# legatus_v0_2_with_notes.net
KiCad netlist of a schematic drawn in EAGLE
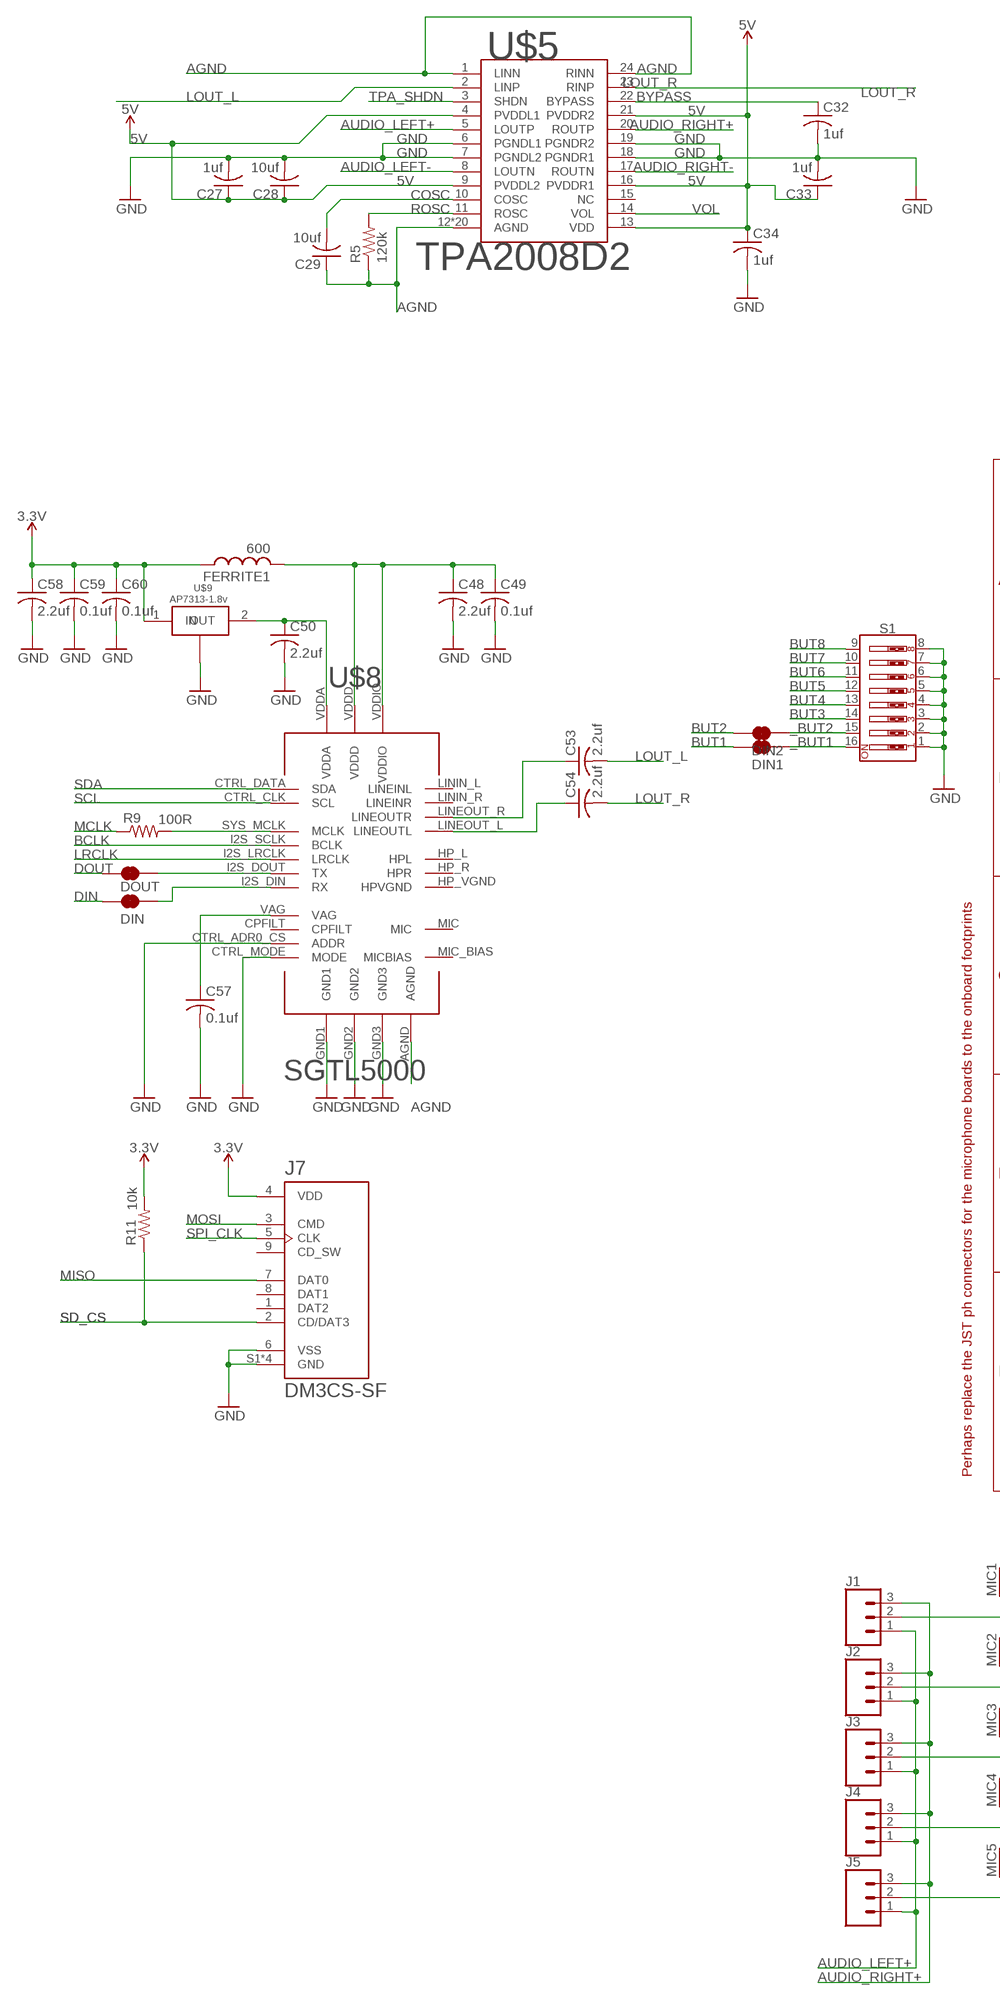
[diagram p0: schematic, sheet 1, part 1 of 2]
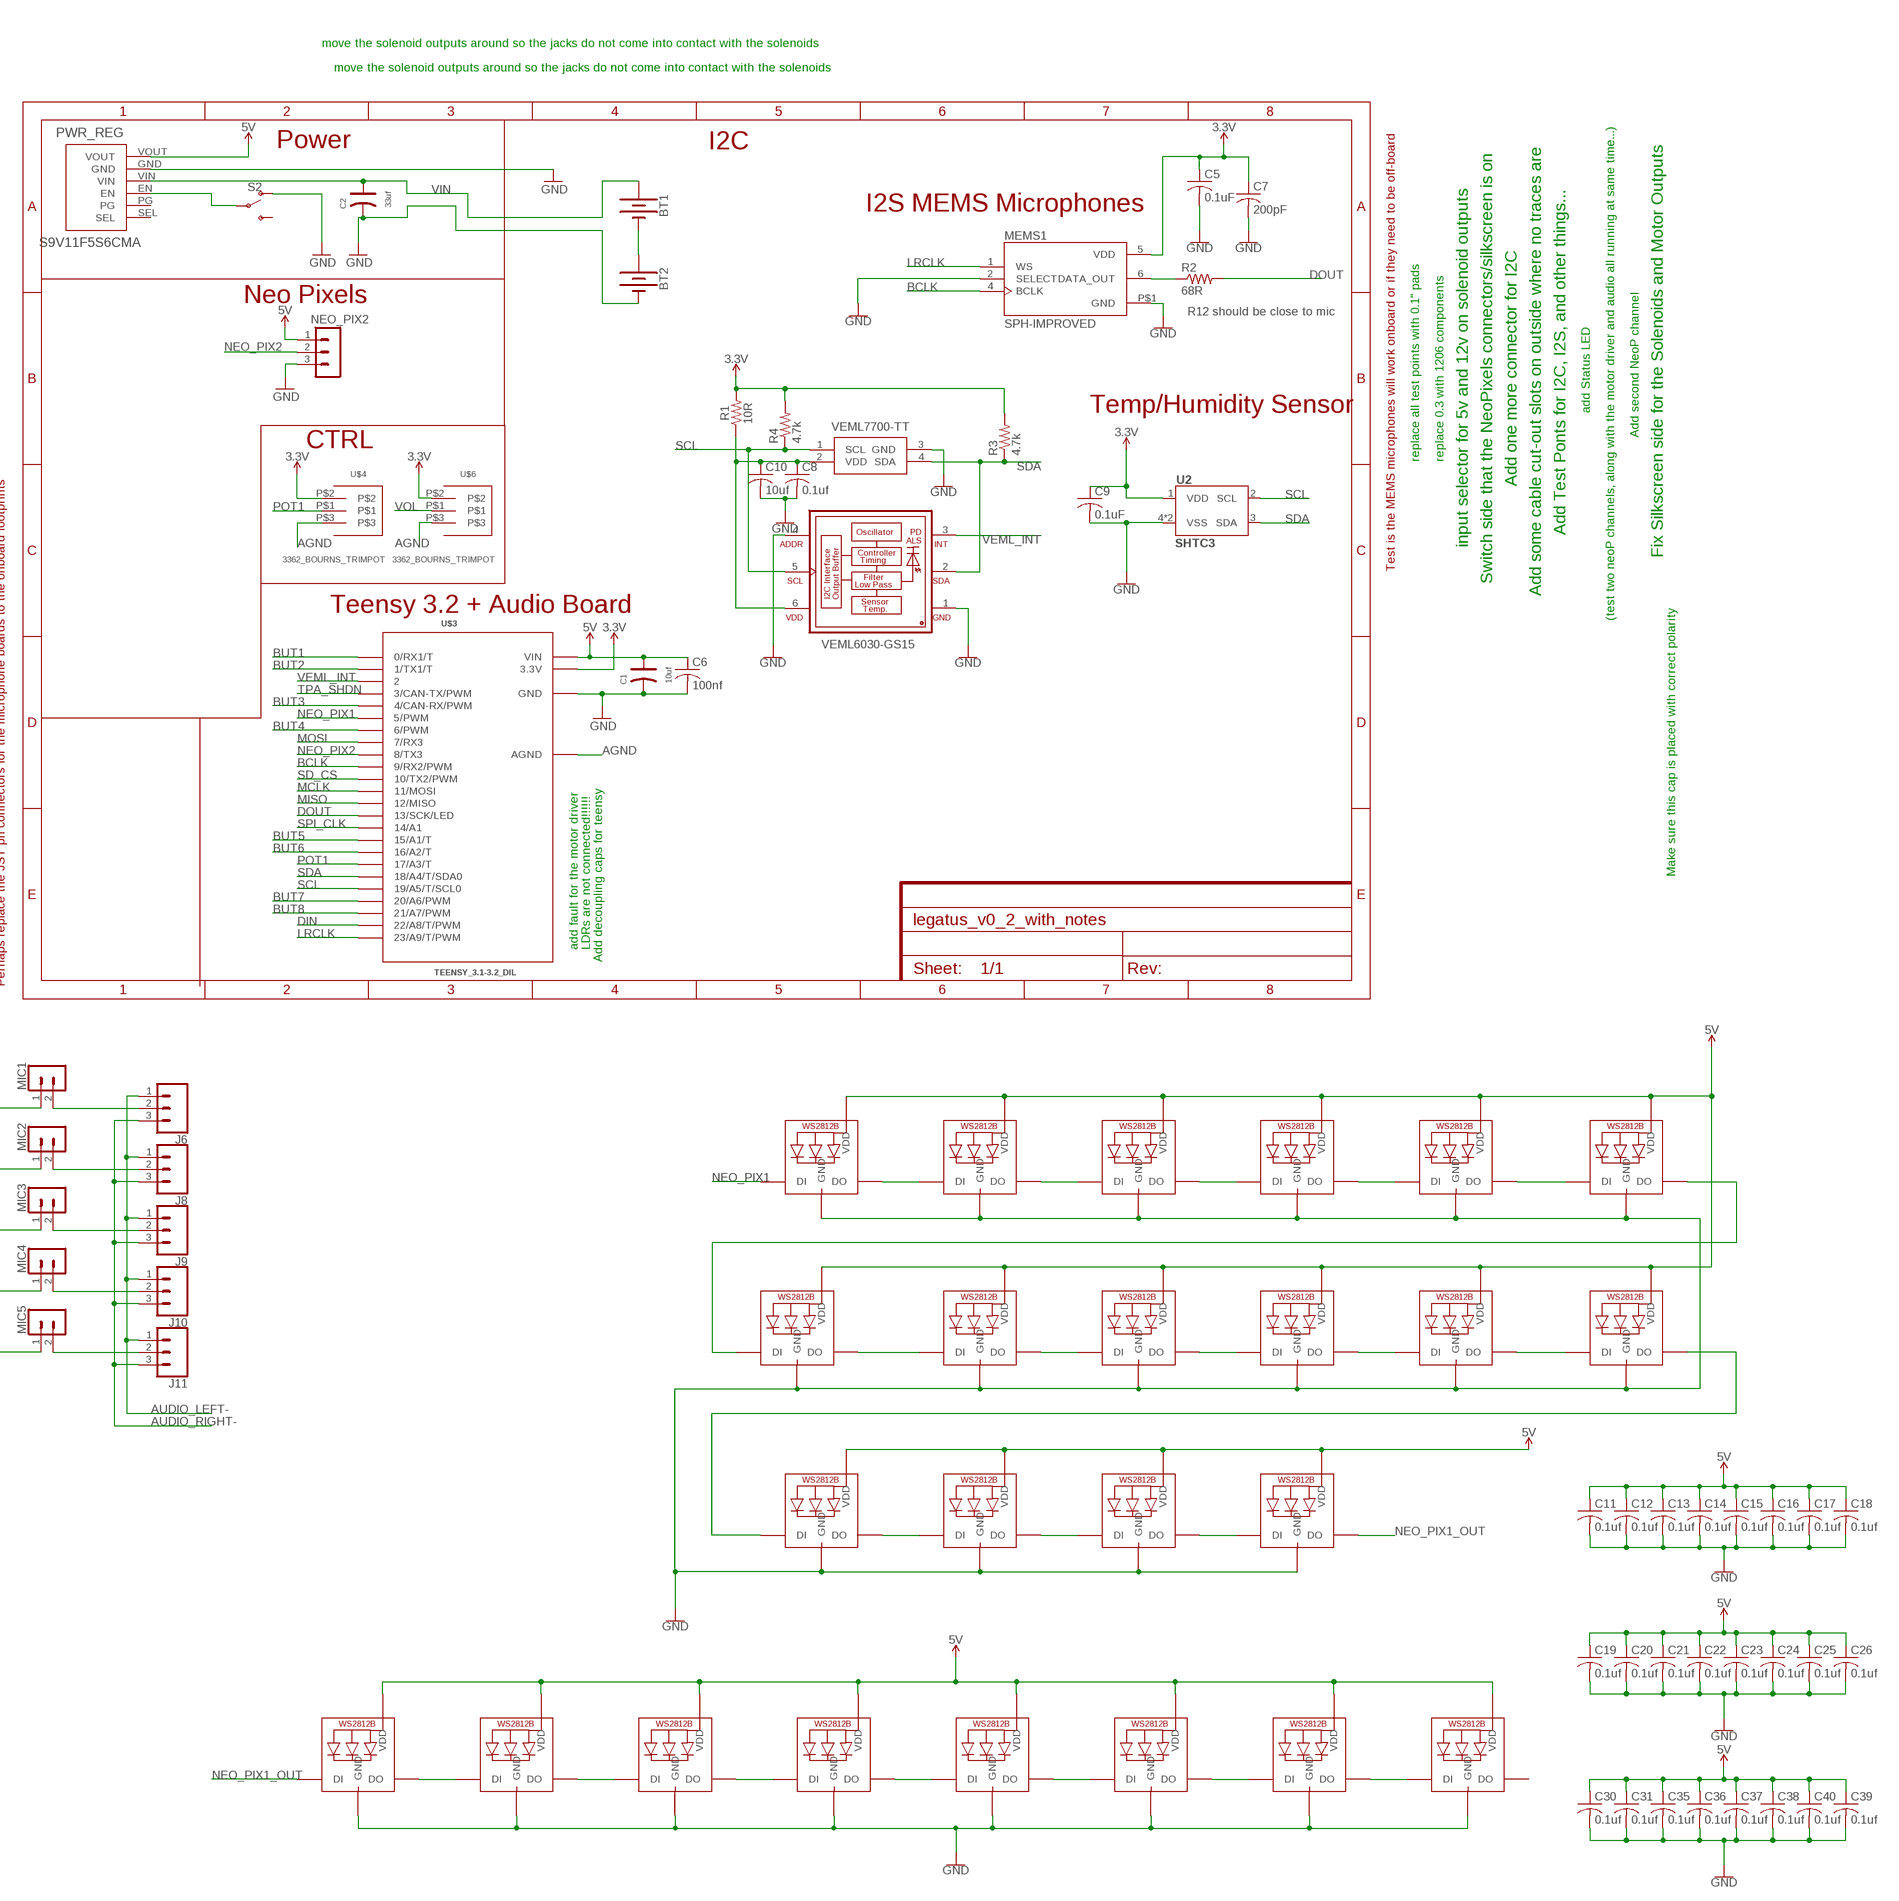
[diagram p1: schematic, sheet 1, part 2 of 2]

(export (version "E")
  (design (tool "Eeschema 10.0.6"))
  (components
    (comp (ref "BT1")
      (value "BATTERY-18650")
      (footprint "eagle-import:BATTERY_18650-HOLDER")
      (libsource (lib "eagle-import") (part "BATTERY-18650"))
    )
    (comp (ref "BT2")
      (value "BATTERY-18650")
      (footprint "eagle-import:BATTERY_18650-HOLDER")
      (libsource (lib "eagle-import") (part "BATTERY-18650"))
    )
    (comp (ref "C1")
      (value "10uf")
      (footprint "eagle-import:PC-D5.3MM")
      (fields (field (name "MPN") "KS 100uF/16V"))
      (libsource (lib "eagle-import") (part "DIP-ALUMINUM-47UF-16V(D5-H7MM)"))
    )
    (comp (ref "C2")
      (value "33uf")
      (footprint "eagle-import:PC-D5.3MM")
      (fields (field (name "MPN") "KS 100uF/16V"))
      (libsource (lib "eagle-import") (part "DIP-ALUMINUM-47UF-16V(D5-H7MM)"))
    )
    (comp (ref "C5")
      (value "0.1uF")
      (footprint "eagle-import:C0805")
      (libsource (lib "eagle-import") (part "rcl_334_C-USC0805"))
    )
    (comp (ref "C6")
      (value "100nf")
      (footprint "eagle-import:C2012")
      (libsource (lib "eagle-import") (part "C-USC2012"))
    )
    (comp (ref "C7")
      (value "200pF")
      (footprint "eagle-import:C0805")
      (libsource (lib "eagle-import") (part "rcl_334_C-USC0805"))
    )
    (comp (ref "C8")
      (value "0.1uf")
      (footprint "eagle-import:C0805")
      (libsource (lib "eagle-import") (part "rcl_334_C-USC0805"))
    )
    (comp (ref "C9")
      (value "0.1uF")
      (footprint "eagle-import:C0805")
      (libsource (lib "eagle-import") (part "rcl_334_C-USC0805"))
    )
    (comp (ref "C10")
      (value "10uf")
      (footprint "eagle-import:C0805")
      (libsource (lib "eagle-import") (part "rcl_334_C-USC0805"))
    )
    (comp (ref "C11")
      (value "0.1uf")
      (footprint "eagle-import:C0805")
      (libsource (lib "eagle-import") (part "rcl_334_C-USC0805"))
    )
    (comp (ref "C12")
      (value "0.1uf")
      (footprint "eagle-import:C0805")
      (libsource (lib "eagle-import") (part "rcl_334_C-USC0805"))
    )
    (comp (ref "C13")
      (value "0.1uf")
      (footprint "eagle-import:C0805")
      (libsource (lib "eagle-import") (part "rcl_334_C-USC0805"))
    )
    (comp (ref "C14")
      (value "0.1uf")
      (footprint "eagle-import:C0805")
      (libsource (lib "eagle-import") (part "rcl_334_C-USC0805"))
    )
    (comp (ref "C15")
      (value "0.1uf")
      (footprint "eagle-import:C0805")
      (libsource (lib "eagle-import") (part "rcl_334_C-USC0805"))
    )
    (comp (ref "C16")
      (value "0.1uf")
      (footprint "eagle-import:C0805")
      (libsource (lib "eagle-import") (part "rcl_334_C-USC0805"))
    )
    (comp (ref "C17")
      (value "0.1uf")
      (footprint "eagle-import:C0805")
      (libsource (lib "eagle-import") (part "rcl_334_C-USC0805"))
    )
    (comp (ref "C18")
      (value "0.1uf")
      (footprint "eagle-import:C0805")
      (libsource (lib "eagle-import") (part "rcl_334_C-USC0805"))
    )
    (comp (ref "C19")
      (value "0.1uf")
      (footprint "eagle-import:C0805")
      (libsource (lib "eagle-import") (part "rcl_334_C-USC0805"))
    )
    (comp (ref "C20")
      (value "0.1uf")
      (footprint "eagle-import:C0805")
      (libsource (lib "eagle-import") (part "rcl_334_C-USC0805"))
    )
    (comp (ref "C21")
      (value "0.1uf")
      (footprint "eagle-import:C0805")
      (libsource (lib "eagle-import") (part "rcl_334_C-USC0805"))
    )
    (comp (ref "C22")
      (value "0.1uf")
      (footprint "eagle-import:C0805")
      (libsource (lib "eagle-import") (part "rcl_334_C-USC0805"))
    )
    (comp (ref "C23")
      (value "0.1uf")
      (footprint "eagle-import:C0805")
      (libsource (lib "eagle-import") (part "rcl_334_C-USC0805"))
    )
    (comp (ref "C24")
      (value "0.1uf")
      (footprint "eagle-import:C0805")
      (libsource (lib "eagle-import") (part "rcl_334_C-USC0805"))
    )
    (comp (ref "C25")
      (value "0.1uf")
      (footprint "eagle-import:C0805")
      (libsource (lib "eagle-import") (part "rcl_334_C-USC0805"))
    )
    (comp (ref "C26")
      (value "0.1uf")
      (footprint "eagle-import:C0805")
      (libsource (lib "eagle-import") (part "rcl_334_C-USC0805"))
    )
    (comp (ref "C27")
      (value "1uf")
      (footprint "eagle-import:C0805")
      (libsource (lib "eagle-import") (part "rcl_334_C-USC0805"))
    )
    (comp (ref "C28")
      (value "10uf")
      (footprint "eagle-import:C0805")
      (libsource (lib "eagle-import") (part "rcl_334_C-USC0805"))
    )
    (comp (ref "C29")
      (value "10uf")
      (footprint "eagle-import:C0805")
      (libsource (lib "eagle-import") (part "rcl_334_C-USC0805"))
    )
    (comp (ref "C30")
      (value "0.1uf")
      (footprint "eagle-import:C0805")
      (libsource (lib "eagle-import") (part "rcl_334_C-USC0805"))
    )
    (comp (ref "C31")
      (value "0.1uf")
      (footprint "eagle-import:C0805")
      (libsource (lib "eagle-import") (part "rcl_334_C-USC0805"))
    )
    (comp (ref "C32")
      (value "1uf")
      (footprint "eagle-import:C0805")
      (libsource (lib "eagle-import") (part "rcl_334_C-USC0805"))
    )
    (comp (ref "C33")
      (value "1uf")
      (footprint "eagle-import:C0805")
      (libsource (lib "eagle-import") (part "rcl_334_C-USC0805"))
    )
    (comp (ref "C34")
      (value "1uf")
      (footprint "eagle-import:C0805")
      (libsource (lib "eagle-import") (part "rcl_334_C-USC0805"))
    )
    (comp (ref "C35")
      (value "0.1uf")
      (footprint "eagle-import:C0805")
      (libsource (lib "eagle-import") (part "rcl_334_C-USC0805"))
    )
    (comp (ref "C36")
      (value "0.1uf")
      (footprint "eagle-import:C0805")
      (libsource (lib "eagle-import") (part "rcl_334_C-USC0805"))
    )
    (comp (ref "C37")
      (value "0.1uf")
      (footprint "eagle-import:C0805")
      (libsource (lib "eagle-import") (part "rcl_334_C-USC0805"))
    )
    (comp (ref "C38")
      (value "0.1uf")
      (footprint "eagle-import:C0805")
      (libsource (lib "eagle-import") (part "rcl_334_C-USC0805"))
    )
    (comp (ref "C39")
      (value "0.1uf")
      (footprint "eagle-import:C0805")
      (libsource (lib "eagle-import") (part "rcl_334_C-USC0805"))
    )
    (comp (ref "C40")
      (value "0.1uf")
      (footprint "eagle-import:C0805")
      (libsource (lib "eagle-import") (part "rcl_334_C-USC0805"))
    )
    (comp (ref "C48")
      (value "2.2uf")
      (footprint "eagle-import:C0805")
      (libsource (lib "eagle-import") (part "rcl_334_C-USC0805"))
    )
    (comp (ref "C49")
      (value "0.1uf")
      (footprint "eagle-import:C0805")
      (libsource (lib "eagle-import") (part "rcl_334_C-USC0805"))
    )
    (comp (ref "C50")
      (value "2.2uf")
      (footprint "eagle-import:C0805")
      (libsource (lib "eagle-import") (part "rcl_334_C-USC0805"))
    )
    (comp (ref "C53")
      (value "2.2uf")
      (footprint "eagle-import:C0805")
      (libsource (lib "eagle-import") (part "rcl_334_C-USC0805"))
    )
    (comp (ref "C54")
      (value "2.2uf")
      (footprint "eagle-import:C0805")
      (libsource (lib "eagle-import") (part "rcl_334_C-USC0805"))
    )
    (comp (ref "C57")
      (value "0.1uf")
      (footprint "eagle-import:C0805")
      (libsource (lib "eagle-import") (part "rcl_334_C-USC0805"))
    )
    (comp (ref "C58")
      (value "2.2uf")
      (footprint "eagle-import:C0805")
      (libsource (lib "eagle-import") (part "rcl_334_C-USC0805"))
    )
    (comp (ref "C59")
      (value "0.1uf")
      (footprint "eagle-import:C0805")
      (libsource (lib "eagle-import") (part "rcl_334_C-USC0805"))
    )
    (comp (ref "C60")
      (value "0.1uf")
      (footprint "eagle-import:C0805")
      (libsource (lib "eagle-import") (part "rcl_334_C-USC0805"))
    )
    (comp (ref "DIN")
      (value "JUMPER-SMT_2_NC_TRACE_SILK")
      (footprint "eagle-import:SMT-JUMPER_2_NC_TRACE_SILK")
      (libsource (lib "eagle-import") (part "JUMPER-SMT_2_NC_TRACE_SILK"))
    )
    (comp (ref "DIN1")
      (value "JUMPER-SMT_2_NC_TRACE_SILK")
      (footprint "eagle-import:SMT-JUMPER_2_NC_TRACE_SILK")
      (libsource (lib "eagle-import") (part "JUMPER-SMT_2_NC_TRACE_SILK"))
    )
    (comp (ref "DIN2")
      (value "JUMPER-SMT_2_NC_TRACE_SILK")
      (footprint "eagle-import:SMT-JUMPER_2_NC_TRACE_SILK")
      (libsource (lib "eagle-import") (part "JUMPER-SMT_2_NC_TRACE_SILK"))
    )
    (comp (ref "DOUT")
      (value "JUMPER-SMT_2_NC_TRACE_SILK")
      (footprint "eagle-import:SMT-JUMPER_2_NC_TRACE_SILK")
      (libsource (lib "eagle-import") (part "JUMPER-SMT_2_NC_TRACE_SILK"))
    )
    (comp (ref "FERRITE1")
      (value "600")
      (footprint "eagle-import:RESC0805_N")
      (libsource (lib "eagle-import") (part "INDUCTOR_0805_N"))
    )
    (comp (ref "J1")
      (value "CONN_03")
      (footprint "eagle-import:1X03")
      (libsource (lib "eagle-import") (part "CONN_03"))
    )
    (comp (ref "J2")
      (value "CONN_03")
      (footprint "eagle-import:1X03")
      (libsource (lib "eagle-import") (part "CONN_03"))
    )
    (comp (ref "J3")
      (value "CONN_03")
      (footprint "eagle-import:1X03")
      (libsource (lib "eagle-import") (part "CONN_03"))
    )
    (comp (ref "J4")
      (value "CONN_03")
      (footprint "eagle-import:1X03")
      (libsource (lib "eagle-import") (part "CONN_03"))
    )
    (comp (ref "J5")
      (value "CONN_03")
      (footprint "eagle-import:1X03")
      (libsource (lib "eagle-import") (part "CONN_03"))
    )
    (comp (ref "J6")
      (value "CONN_03")
      (footprint "eagle-import:1X03")
      (libsource (lib "eagle-import") (part "CONN_03"))
    )
    (comp (ref "J7")
      (value "DM3CS-SF")
      (footprint "eagle-import:HRS_DM3CS-SF")
      (fields (field (name "MF") "Hirose"))
      (libsource (lib "eagle-import") (part "DM3CS-SF"))
    )
    (comp (ref "J8")
      (value "CONN_03")
      (footprint "eagle-import:1X03")
      (libsource (lib "eagle-import") (part "CONN_03"))
    )
    (comp (ref "J9")
      (value "CONN_03")
      (footprint "eagle-import:1X03")
      (libsource (lib "eagle-import") (part "CONN_03"))
    )
    (comp (ref "J10")
      (value "CONN_03")
      (footprint "eagle-import:1X03")
      (libsource (lib "eagle-import") (part "CONN_03"))
    )
    (comp (ref "J11")
      (value "CONN_03")
      (footprint "eagle-import:1X03")
      (libsource (lib "eagle-import") (part "CONN_03"))
    )
    (comp (ref "LED1")
      (value "WS2812B_5050N")
      (footprint "eagle-import:WS2812B-NARROW")
      (libsource (lib "eagle-import") (part "WS2812B_5050N"))
    )
    (comp (ref "LED2")
      (value "WS2812B_5050N")
      (footprint "eagle-import:WS2812B-NARROW")
      (libsource (lib "eagle-import") (part "WS2812B_5050N"))
    )
    (comp (ref "LED3")
      (value "WS2812B_5050N")
      (footprint "eagle-import:WS2812B-NARROW")
      (libsource (lib "eagle-import") (part "WS2812B_5050N"))
    )
    (comp (ref "LED4")
      (value "WS2812B_5050N")
      (footprint "eagle-import:WS2812B-NARROW")
      (libsource (lib "eagle-import") (part "WS2812B_5050N"))
    )
    (comp (ref "LED5")
      (value "WS2812B_5050N")
      (footprint "eagle-import:WS2812B-NARROW")
      (libsource (lib "eagle-import") (part "WS2812B_5050N"))
    )
    (comp (ref "LED6")
      (value "WS2812B_5050N")
      (footprint "eagle-import:WS2812B-NARROW")
      (libsource (lib "eagle-import") (part "WS2812B_5050N"))
    )
    (comp (ref "LED7")
      (value "WS2812B_5050N")
      (footprint "eagle-import:WS2812B-NARROW")
      (libsource (lib "eagle-import") (part "WS2812B_5050N"))
    )
    (comp (ref "LED8")
      (value "WS2812B_5050N")
      (footprint "eagle-import:WS2812B-NARROW")
      (libsource (lib "eagle-import") (part "WS2812B_5050N"))
    )
    (comp (ref "LED9")
      (value "WS2812B_5050N")
      (footprint "eagle-import:WS2812B-NARROW")
      (libsource (lib "eagle-import") (part "WS2812B_5050N"))
    )
    (comp (ref "LED10")
      (value "WS2812B_5050N")
      (footprint "eagle-import:WS2812B-NARROW")
      (libsource (lib "eagle-import") (part "WS2812B_5050N"))
    )
    (comp (ref "LED11")
      (value "WS2812B_5050N")
      (footprint "eagle-import:WS2812B-NARROW")
      (libsource (lib "eagle-import") (part "WS2812B_5050N"))
    )
    (comp (ref "LED12")
      (value "WS2812B_5050N")
      (footprint "eagle-import:WS2812B-NARROW")
      (libsource (lib "eagle-import") (part "WS2812B_5050N"))
    )
    (comp (ref "LED13")
      (value "WS2812B_5050N")
      (footprint "eagle-import:WS2812B-NARROW")
      (libsource (lib "eagle-import") (part "WS2812B_5050N"))
    )
    (comp (ref "LED14")
      (value "WS2812B_5050N")
      (footprint "eagle-import:WS2812B-NARROW")
      (libsource (lib "eagle-import") (part "WS2812B_5050N"))
    )
    (comp (ref "LED15")
      (value "WS2812B_5050N")
      (footprint "eagle-import:WS2812B-NARROW")
      (libsource (lib "eagle-import") (part "WS2812B_5050N"))
    )
    (comp (ref "LED16")
      (value "WS2812B_5050N")
      (footprint "eagle-import:WS2812B-NARROW")
      (libsource (lib "eagle-import") (part "WS2812B_5050N"))
    )
    (comp (ref "LED17")
      (value "WS2812B_5050N")
      (footprint "eagle-import:WS2812B-NARROW")
      (libsource (lib "eagle-import") (part "WS2812B_5050N"))
    )
    (comp (ref "LED18")
      (value "WS2812B_5050N")
      (footprint "eagle-import:WS2812B-NARROW")
      (libsource (lib "eagle-import") (part "WS2812B_5050N"))
    )
    (comp (ref "LED19")
      (value "WS2812B_5050N")
      (footprint "eagle-import:WS2812B-NARROW")
      (libsource (lib "eagle-import") (part "WS2812B_5050N"))
    )
    (comp (ref "LED20")
      (value "WS2812B_5050N")
      (footprint "eagle-import:WS2812B-NARROW")
      (libsource (lib "eagle-import") (part "WS2812B_5050N"))
    )
    (comp (ref "LED21")
      (value "WS2812B_5050N")
      (footprint "eagle-import:WS2812B-NARROW")
      (libsource (lib "eagle-import") (part "WS2812B_5050N"))
    )
    (comp (ref "LED22")
      (value "WS2812B_5050N")
      (footprint "eagle-import:WS2812B-NARROW")
      (libsource (lib "eagle-import") (part "WS2812B_5050N"))
    )
    (comp (ref "LED23")
      (value "WS2812B_5050N")
      (footprint "eagle-import:WS2812B-NARROW")
      (libsource (lib "eagle-import") (part "WS2812B_5050N"))
    )
    (comp (ref "LED24")
      (value "WS2812B_5050N")
      (footprint "eagle-import:WS2812B-NARROW")
      (libsource (lib "eagle-import") (part "WS2812B_5050N"))
    )
    (comp (ref "MEMS1")
      (value "SPH-IMPROVED")
      (footprint "eagle-import:MIC_SPH0645LM4H-B_LARGER_RING")
      (libsource (lib "eagle-import") (part "SPH-IMPROVED"))
    )
    (comp (ref "MIC1")
      (value "B2B-PH-K")
      (footprint "eagle-import:B2B-PH-K")
      (libsource (lib "eagle-import") (part "B2B-PH-K"))
    )
    (comp (ref "MIC2")
      (value "B2B-PH-K")
      (footprint "eagle-import:B2B-PH-K")
      (libsource (lib "eagle-import") (part "B2B-PH-K"))
    )
    (comp (ref "MIC3")
      (value "B2B-PH-K")
      (footprint "eagle-import:B2B-PH-K")
      (libsource (lib "eagle-import") (part "B2B-PH-K"))
    )
    (comp (ref "MIC4")
      (value "B2B-PH-K")
      (footprint "eagle-import:B2B-PH-K")
      (libsource (lib "eagle-import") (part "B2B-PH-K"))
    )
    (comp (ref "MIC5")
      (value "B2B-PH-K")
      (footprint "eagle-import:B2B-PH-K")
      (libsource (lib "eagle-import") (part "B2B-PH-K"))
    )
    (comp (ref "NEO_PIX2")
      (value "B3B-PH-K")
      (footprint "eagle-import:B3B-PH-K")
      (libsource (lib "eagle-import") (part "B3B-PH-K"))
    )
    (comp (ref "PWR_REG")
      (value "S9V11F5S6CMA")
      (footprint "eagle-import:S9V11F3S5CMA")
      (libsource (lib "eagle-import") (part "S9V11F5S6CMA"))
    )
    (comp (ref "R1")
      (value "10R")
      (footprint "eagle-import:R0805")
      (libsource (lib "eagle-import") (part "audio amplifier example_970892_R-US_R0805"))
    )
    (comp (ref "R2")
      (value "68R")
      (footprint "eagle-import:M0805")
      (libsource (lib "eagle-import") (part "R-US_M0805"))
    )
    (comp (ref "R3")
      (value "4.7k")
      (footprint "eagle-import:M0805")
      (libsource (lib "eagle-import") (part "R-US_M0805"))
    )
    (comp (ref "R4")
      (value "4.7k")
      (footprint "eagle-import:M0805")
      (libsource (lib "eagle-import") (part "R-US_M0805"))
    )
    (comp (ref "R5")
      (value "120k")
      (footprint "eagle-import:M0805")
      (libsource (lib "eagle-import") (part "R-US_M0805"))
    )
    (comp (ref "R9")
      (value "100R")
      (footprint "eagle-import:M0805")
      (libsource (lib "eagle-import") (part "rcl_R-US_M0805"))
    )
    (comp (ref "R11")
      (value "10k")
      (footprint "eagle-import:M0805")
      (libsource (lib "eagle-import") (part "rcl_R-US_M0805"))
    )
    (comp (ref "S1")
      (value "DIP-08-PTH")
      (footprint "eagle-import:DIPSWITCH-08")
      (libsource (lib "eagle-import") (part "DIP-08-PTH"))
    )
    (comp (ref "S2")
      (value "SWITCH-SPDT-PTH-11.6X4.0MM-LOCK")
      (footprint "eagle-import:SWITCH_SPDT_PTH_11.6X4.0MM_LOCK")
      (libsource (lib "eagle-import") (part "SWITCH-SPDT-PTH-11.6X4.0MM-LOCK"))
    )
    (comp (ref "U$3")
      (value "TEENSY_3.1-3.2_DIL")
      (footprint "eagle-import:TEENSY_3.0-3.2&LC_DIL")
      (libsource (lib "eagle-import") (part "TEENSY_3.1-3.2_DIL"))
    )
    (comp (ref "U$4")
      (value "3362_BOURNS_TRIMPOT")
      (footprint "eagle-import:3362_BOURNS_TRIMPOT")
      (libsource (lib "eagle-import") (part "3362_BOURNS_TRIMPOT"))
    )
    (comp (ref "U$5")
      (value "TPA2008D2")
      (footprint "eagle-import:PWP-TSSOP24")
      (libsource (lib "eagle-import") (part "TPA2008D2"))
    )
    (comp (ref "U$6")
      (value "3362_BOURNS_TRIMPOT")
      (footprint "eagle-import:3362_BOURNS_TRIMPOT")
      (libsource (lib "eagle-import") (part "3362_BOURNS_TRIMPOT"))
    )
    (comp (ref "U$8")
      (value "SGTL5000")
      (footprint "eagle-import:QFN-32-5X5MM")
      (libsource (lib "eagle-import") (part "SGTL5000"))
    )
    (comp (ref "U$9")
      (value "AP7313-1.8v")
      (footprint "eagle-import:SOT-23")
      (libsource (lib "eagle-import") (part "AP7313"))
    )
    (comp (ref "U2")
      (value "SHTC3")
      (footprint "eagle-import:SHTC3")
      (libsource (lib "eagle-import") (part "SHTC3"))
    )
    (comp (ref "VEML1")
      (value "VEML7700-TT")
      (footprint "eagle-import:VEML7700")
      (fields (field (name "MOUSER_PART_NUMBER") "78-VEML7700-TT") (field (name "RS_PART_NUMBER") "1226791P"))
      (libsource (lib "eagle-import") (part "VEML7700-TT"))
    )
    (comp (ref "VMEL1")
      (value "VEML6030-GS15")
      (footprint "eagle-import:VISHAY_VEML6030_2X2X0.87")
      (fields (field (name "MF") "Vishay Semiconductor"))
      (libsource (lib "eagle-import") (part "VEML6030-GS15"))
    )
  )
  (nets
    (net (code "1") (name "/AGND") (class "Default")
      (node (ref "C29") (pin "1") (pinfunction "1_1") (pintype "passive"))
      (node (ref "R5") (pin "1") (pinfunction "1_1") (pintype "passive"))
      (node (ref "U$3") (pin "AGND") (pinfunction "AGND_AGND") (pintype "power_in"))
      (node (ref "U$4") (pin "P$3") (pinfunction "P$3_P$3") (pintype "bidirectional"))
      (node (ref "U$5") (pin "1") (pinfunction "LINN_1") (pintype "bidirectional"))
      (node (ref "U$5") (pin "12") (pinfunction "AGND_12") (pintype "bidirectional"))
      (node (ref "U$5") (pin "24") (pinfunction "RINN_24") (pintype "bidirectional"))
      (node (ref "U$5") (pin "EXP") (pinfunction "AGND_EXP") (pintype "bidirectional"))
      (node (ref "U$5") (pin "EXP@1") (pinfunction "AGND_EXP@1") (pintype "bidirectional"))
      (node (ref "U$5") (pin "EXP@10") (pinfunction "AGND_EXP@10") (pintype "bidirectional"))
      (node (ref "U$5") (pin "EXP@11") (pinfunction "AGND_EXP@11") (pintype "bidirectional"))
      (node (ref "U$5") (pin "EXP@12") (pinfunction "AGND_EXP@12") (pintype "bidirectional"))
      (node (ref "U$5") (pin "EXP@13") (pinfunction "AGND_EXP@13") (pintype "bidirectional"))
      (node (ref "U$5") (pin "EXP@14") (pinfunction "AGND_EXP@14") (pintype "bidirectional"))
      (node (ref "U$5") (pin "EXP@15") (pinfunction "AGND_EXP@15") (pintype "bidirectional"))
      (node (ref "U$5") (pin "EXP@16") (pinfunction "AGND_EXP@16") (pintype "bidirectional"))
      (node (ref "U$5") (pin "EXP@17") (pinfunction "AGND_EXP@17") (pintype "bidirectional"))
      (node (ref "U$5") (pin "EXP@18") (pinfunction "AGND_EXP@18") (pintype "bidirectional"))
      (node (ref "U$5") (pin "EXP@2") (pinfunction "AGND_EXP@2") (pintype "bidirectional"))
      (node (ref "U$5") (pin "EXP@3") (pinfunction "AGND_EXP@3") (pintype "bidirectional"))
      (node (ref "U$5") (pin "EXP@4") (pinfunction "AGND_EXP@4") (pintype "bidirectional"))
      (node (ref "U$5") (pin "EXP@5") (pinfunction "AGND_EXP@5") (pintype "bidirectional"))
      (node (ref "U$5") (pin "EXP@6") (pinfunction "AGND_EXP@6") (pintype "bidirectional"))
      (node (ref "U$5") (pin "EXP@7") (pinfunction "AGND_EXP@7") (pintype "bidirectional"))
      (node (ref "U$5") (pin "EXP@8") (pinfunction "AGND_EXP@8") (pintype "bidirectional"))
      (node (ref "U$5") (pin "EXP@9") (pinfunction "AGND_EXP@9") (pintype "bidirectional"))
      (node (ref "U$6") (pin "P$3") (pinfunction "P$3_P$3") (pintype "bidirectional"))
      (node (ref "U$8") (pin "AGND") (pinfunction "AGND_AGND") (pintype "bidirectional"))
    )
    (net (code "2") (name "/AUDIO_LEFT+") (class "Default")
      (node (ref "J1") (pin "1") (pinfunction "1_1") (pintype "passive"))
      (node (ref "J2") (pin "1") (pinfunction "1_1") (pintype "passive"))
      (node (ref "J3") (pin "1") (pinfunction "1_1") (pintype "passive"))
      (node (ref "J4") (pin "1") (pinfunction "1_1") (pintype "passive"))
      (node (ref "J5") (pin "1") (pinfunction "1_1") (pintype "passive"))
      (node (ref "U$5") (pin "5") (pinfunction "LOUTP_5") (pintype "bidirectional"))
    )
    (net (code "3") (name "/AUDIO_LEFT-") (class "Default")
      (node (ref "J10") (pin "1") (pinfunction "1_1") (pintype "passive"))
      (node (ref "J11") (pin "1") (pinfunction "1_1") (pintype "passive"))
      (node (ref "J6") (pin "1") (pinfunction "1_1") (pintype "passive"))
      (node (ref "J8") (pin "1") (pinfunction "1_1") (pintype "passive"))
      (node (ref "J9") (pin "1") (pinfunction "1_1") (pintype "passive"))
      (node (ref "U$5") (pin "8") (pinfunction "LOUTN_8") (pintype "bidirectional"))
    )
    (net (code "4") (name "/AUDIO_RIGHT+") (class "Default")
      (node (ref "J1") (pin "3") (pinfunction "3_3") (pintype "passive"))
      (node (ref "J2") (pin "3") (pinfunction "3_3") (pintype "passive"))
      (node (ref "J3") (pin "3") (pinfunction "3_3") (pintype "passive"))
      (node (ref "J4") (pin "3") (pinfunction "3_3") (pintype "passive"))
      (node (ref "J5") (pin "3") (pinfunction "3_3") (pintype "passive"))
      (node (ref "U$5") (pin "20") (pinfunction "ROUTP_20") (pintype "bidirectional"))
    )
    (net (code "5") (name "/AUDIO_RIGHT-") (class "Default")
      (node (ref "J10") (pin "3") (pinfunction "3_3") (pintype "passive"))
      (node (ref "J11") (pin "3") (pinfunction "3_3") (pintype "passive"))
      (node (ref "J6") (pin "3") (pinfunction "3_3") (pintype "passive"))
      (node (ref "J8") (pin "3") (pinfunction "3_3") (pintype "passive"))
      (node (ref "J9") (pin "3") (pinfunction "3_3") (pintype "passive"))
      (node (ref "U$5") (pin "17") (pinfunction "ROUTN_17") (pintype "bidirectional"))
    )
    (net (code "6") (name "/BCLK") (class "Default")
      (node (ref "MEMS1") (pin "4") (pinfunction "BCLK_4") (pintype "input"))
      (node (ref "U$3") (pin "9") (pinfunction "9/RX2/PWM_9") (pintype "bidirectional"))
      (node (ref "U$8") (pin "I2S_SCLK") (pinfunction "BCLK_I2S_SCLK") (pintype "bidirectional"))
    )
    (net (code "7") (name "/BUT1") (class "Default")
      (node (ref "DIN1") (pin "1") (pinfunction "1_1") (pintype "passive"))
      (node (ref "U$3") (pin "0") (pinfunction "0/RX1/T_0") (pintype "bidirectional"))
    )
    (net (code "8") (name "/BUT2") (class "Default")
      (node (ref "DIN2") (pin "1") (pinfunction "1_1") (pintype "passive"))
      (node (ref "U$3") (pin "1") (pinfunction "1/TX1/T_1") (pintype "bidirectional"))
    )
    (net (code "9") (name "/BUT3") (class "Default")
      (node (ref "S1") (pin "14") (pinfunction "14_14") (pintype "passive"))
      (node (ref "U$3") (pin "4") (pinfunction "4/CAN-RX/PWM_4") (pintype "bidirectional"))
    )
    (net (code "10") (name "/BUT4") (class "Default")
      (node (ref "S1") (pin "13") (pinfunction "13_13") (pintype "passive"))
      (node (ref "U$3") (pin "6") (pinfunction "6/PWM_6") (pintype "bidirectional"))
    )
    (net (code "11") (name "/BUT5") (class "Default")
      (node (ref "S1") (pin "12") (pinfunction "12_12") (pintype "passive"))
      (node (ref "U$3") (pin "15/A1") (pinfunction "15/A1/T_15/A1") (pintype "bidirectional"))
    )
    (net (code "12") (name "/BUT6") (class "Default")
      (node (ref "S1") (pin "11") (pinfunction "11_11") (pintype "passive"))
      (node (ref "U$3") (pin "16/A2") (pinfunction "16/A2/T_16/A2") (pintype "bidirectional"))
    )
    (net (code "13") (name "/BUT7") (class "Default")
      (node (ref "S1") (pin "10") (pinfunction "10_10") (pintype "passive"))
      (node (ref "U$3") (pin "20/A6") (pinfunction "20/A6/PWM_20/A6") (pintype "bidirectional"))
    )
    (net (code "14") (name "/BUT8") (class "Default")
      (node (ref "S1") (pin "9") (pinfunction "9_9") (pintype "passive"))
      (node (ref "U$3") (pin "21/A7") (pinfunction "21/A7/PWM_21/A7") (pintype "bidirectional"))
    )
    (net (code "15") (name "/BYPASS") (class "Default")
      (node (ref "C32") (pin "1") (pinfunction "1_1") (pintype "passive"))
      (node (ref "U$5") (pin "22") (pinfunction "BYPASS_22") (pintype "bidirectional"))
    )
    (net (code "16") (name "/COSC") (class "Default")
      (node (ref "C29") (pin "2") (pinfunction "2_2") (pintype "passive"))
      (node (ref "U$5") (pin "10") (pinfunction "COSC_10") (pintype "bidirectional"))
    )
    (net (code "17") (name "/DIN") (class "Default")
      (node (ref "DIN") (pin "1") (pinfunction "1_1") (pintype "passive"))
      (node (ref "U$3") (pin "22/A8") (pinfunction "22/A8/T/PWM_22/A8") (pintype "bidirectional"))
    )
    (net (code "18") (name "/DOUT") (class "Default")
      (node (ref "DOUT") (pin "1") (pinfunction "1_1") (pintype "passive"))
      (node (ref "R2") (pin "2") (pinfunction "2_2") (pintype "passive"))
      (node (ref "U$3") (pin "13") (pinfunction "13/SCK/LED_13") (pintype "bidirectional"))
    )
    (net (code "19") (name "/LOUT_L") (class "Default")
      (node (ref "C53") (pin "2") (pinfunction "2_2") (pintype "passive"))
      (node (ref "U$5") (pin "2") (pinfunction "LINP_2") (pintype "bidirectional"))
    )
    (net (code "20") (name "/LOUT_R") (class "Default")
      (node (ref "C54") (pin "2") (pinfunction "2_2") (pintype "passive"))
      (node (ref "U$5") (pin "23") (pinfunction "RINP_23") (pintype "bidirectional"))
    )
    (net (code "21") (name "/LRCLK") (class "Default")
      (node (ref "MEMS1") (pin "1") (pinfunction "WS_1") (pintype "input"))
      (node (ref "U$3") (pin "23/A9") (pinfunction "23/A9/T/PWM_23/A9") (pintype "bidirectional"))
      (node (ref "U$8") (pin "I2S_LRCLK") (pinfunction "LRCLK_I2S_LRCLK") (pintype "bidirectional"))
    )
    (net (code "22") (name "/MCLK") (class "Default")
      (node (ref "R9") (pin "1") (pinfunction "1_1") (pintype "passive"))
      (node (ref "U$3") (pin "11") (pinfunction "11/MOSI_11") (pintype "bidirectional"))
    )
    (net (code "23") (name "/MISO") (class "Default")
      (node (ref "J7") (pin "7") (pinfunction "DAT0_7") (pintype "passive"))
      (node (ref "U$3") (pin "12") (pinfunction "12/MISO_12") (pintype "bidirectional"))
    )
    (net (code "24") (name "/MOSI") (class "Default")
      (node (ref "J7") (pin "3") (pinfunction "CMD_3") (pintype "passive"))
      (node (ref "U$3") (pin "7") (pinfunction "7/RX3_7") (pintype "bidirectional"))
    )
    (net (code "25") (name "/NEO_PIX1") (class "Default")
      (node (ref "LED1") (pin "4-DIN") (pinfunction "DI_4-DIN") (pintype "input"))
      (node (ref "U$3") (pin "5") (pinfunction "5/PWM_5") (pintype "bidirectional"))
    )
    (net (code "26") (name "/NEO_PIX1_OUT") (class "Default")
      (node (ref "LED16") (pin "2-DOUT") (pinfunction "DO_2-DOUT") (pintype "output"))
      (node (ref "LED17") (pin "4-DIN") (pinfunction "DI_4-DIN") (pintype "input"))
    )
    (net (code "27") (name "/NEO_PIX2") (class "Default")
      (node (ref "NEO_PIX2") (pin "2") (pinfunction "2_2") (pintype "passive"))
      (node (ref "U$3") (pin "8") (pinfunction "8/TX3_8") (pintype "bidirectional"))
    )
    (net (code "28") (name "/POT1") (class "Default")
      (node (ref "U$3") (pin "17/A3") (pinfunction "17/A3/T_17/A3") (pintype "bidirectional"))
      (node (ref "U$4") (pin "P$1") (pinfunction "P$1_P$1") (pintype "bidirectional"))
    )
    (net (code "29") (name "/ROSC") (class "Default")
      (node (ref "R5") (pin "2") (pinfunction "2_2") (pintype "passive"))
      (node (ref "U$5") (pin "11") (pinfunction "ROSC_11") (pintype "bidirectional"))
    )
    (net (code "30") (name "/SCL") (class "Default")
      (node (ref "R4") (pin "1") (pinfunction "1_1") (pintype "passive"))
      (node (ref "U$3") (pin "19/A5") (pinfunction "19/A5/T/SCL0_19/A5") (pintype "bidirectional"))
      (node (ref "U$8") (pin "CTRL_CLK") (pinfunction "SCL_CTRL_CLK") (pintype "bidirectional"))
      (node (ref "U2") (pin "2") (pinfunction "SCL_2") (pintype "bidirectional"))
      (node (ref "VEML1") (pin "1") (pinfunction "SCL_1") (pintype "bidirectional"))
      (node (ref "VMEL1") (pin "5") (pinfunction "SCL_5") (pintype "input"))
    )
    (net (code "31") (name "/SDA") (class "Default")
      (node (ref "R3") (pin "1") (pinfunction "1_1") (pintype "passive"))
      (node (ref "U$3") (pin "18/A4") (pinfunction "18/A4/T/SDA0_18/A4") (pintype "bidirectional"))
      (node (ref "U$8") (pin "CTRL_DATA") (pinfunction "SDA_CTRL_DATA") (pintype "bidirectional"))
      (node (ref "U2") (pin "3") (pinfunction "SDA_3") (pintype "bidirectional"))
      (node (ref "VEML1") (pin "4") (pinfunction "SDA_4") (pintype "bidirectional"))
      (node (ref "VMEL1") (pin "2") (pinfunction "SDA_2") (pintype "bidirectional"))
    )
    (net (code "32") (name "/SD_CS") (class "Default")
      (node (ref "J7") (pin "2") (pinfunction "CD/DAT3_2") (pintype "passive"))
      (node (ref "R11") (pin "1") (pinfunction "1_1") (pintype "passive"))
      (node (ref "U$3") (pin "10") (pinfunction "10/TX2/PWM_10") (pintype "bidirectional"))
    )
    (net (code "33") (name "/SPI_CLK") (class "Default")
      (node (ref "J7") (pin "5") (pinfunction "CLK_5") (pintype "passive"))
      (node (ref "U$3") (pin "14/A0") (pinfunction "14/A1_14/A0") (pintype "bidirectional"))
    )
    (net (code "34") (name "/TPA_SHDN") (class "Default")
      (node (ref "U$3") (pin "3") (pinfunction "3/CAN-TX/PWM_3") (pintype "bidirectional"))
      (node (ref "U$5") (pin "3") (pinfunction "SHDN_3") (pintype "bidirectional"))
    )
    (net (code "35") (name "/VEML_INT") (class "Default")
      (node (ref "U$3") (pin "2") (pinfunction "2_2") (pintype "bidirectional"))
      (node (ref "VMEL1") (pin "3") (pinfunction "INT_3") (pintype "output"))
    )
    (net (code "36") (name "/VIN") (class "Default")
      (node (ref "BT1") (pin "PWR@1") (pinfunction "+_PWR@1") (pintype "power_in"))
      (node (ref "C2") (pin "+") (pinfunction "+_+") (pintype "passive"))
      (node (ref "PWR_REG") (pin "VIN") (pinfunction "VIN_VIN") (pintype "bidirectional"))
    )
    (net (code "37") (name "/VOL") (class "Default")
      (node (ref "U$5") (pin "14") (pinfunction "VOL_14") (pintype "bidirectional"))
      (node (ref "U$6") (pin "P$1") (pinfunction "P$1_P$1") (pintype "bidirectional"))
    )
    (net (code "38") (name "/_BUT1") (class "Default")
      (node (ref "DIN1") (pin "2") (pinfunction "2_2") (pintype "passive"))
      (node (ref "S1") (pin "16") (pinfunction "16_16") (pintype "passive"))
    )
    (net (code "39") (name "/_BUT2") (class "Default")
      (node (ref "DIN2") (pin "2") (pinfunction "2_2") (pintype "passive"))
      (node (ref "S1") (pin "15") (pinfunction "15_15") (pintype "passive"))
    )
    (net (code "40") (name "3.3V") (class "Default")
      (node (ref "C5") (pin "1") (pinfunction "1_1") (pintype "passive"))
      (node (ref "C58") (pin "1") (pinfunction "1_1") (pintype "passive"))
      (node (ref "C59") (pin "1") (pinfunction "1_1") (pintype "passive"))
      (node (ref "C60") (pin "1") (pinfunction "1_1") (pintype "passive"))
      (node (ref "C7") (pin "1") (pinfunction "1_1") (pintype "passive"))
      (node (ref "C9") (pin "1") (pinfunction "1_1") (pintype "passive"))
      (node (ref "FERRITE1") (pin "1") (pinfunction "1_1") (pintype "passive"))
      (node (ref "J7") (pin "4") (pinfunction "VDD_4") (pintype "passive"))
      (node (ref "MEMS1") (pin "5") (pinfunction "VDD_5") (pintype "power_in"))
      (node (ref "R1") (pin "2") (pinfunction "2_2") (pintype "passive"))
      (node (ref "R11") (pin "2") (pinfunction "2_2") (pintype "passive"))
      (node (ref "R3") (pin "2") (pinfunction "2_2") (pintype "passive"))
      (node (ref "R4") (pin "2") (pinfunction "2_2") (pintype "passive"))
      (node (ref "U$3") (pin "3.3V") (pinfunction "3.3V_3.3V") (pintype "power_in"))
      (node (ref "U$4") (pin "P$2") (pinfunction "P$2_P$2") (pintype "bidirectional"))
      (node (ref "U$6") (pin "P$2") (pinfunction "P$2_P$2") (pintype "bidirectional"))
      (node (ref "U$9") (pin "1") (pinfunction "IN_1") (pintype "bidirectional"))
      (node (ref "U2") (pin "1") (pinfunction "VDD_1") (pintype "bidirectional"))
    )
    (net (code "41") (name "5V") (class "Default")
      (node (ref "C1") (pin "+") (pinfunction "+_+") (pintype "passive"))
      (node (ref "C11") (pin "1") (pinfunction "1_1") (pintype "passive"))
      (node (ref "C12") (pin "1") (pinfunction "1_1") (pintype "passive"))
      (node (ref "C13") (pin "1") (pinfunction "1_1") (pintype "passive"))
      (node (ref "C14") (pin "1") (pinfunction "1_1") (pintype "passive"))
      (node (ref "C15") (pin "1") (pinfunction "1_1") (pintype "passive"))
      (node (ref "C16") (pin "1") (pinfunction "1_1") (pintype "passive"))
      (node (ref "C17") (pin "1") (pinfunction "1_1") (pintype "passive"))
      (node (ref "C18") (pin "1") (pinfunction "1_1") (pintype "passive"))
      (node (ref "C19") (pin "1") (pinfunction "1_1") (pintype "passive"))
      (node (ref "C20") (pin "1") (pinfunction "1_1") (pintype "passive"))
      (node (ref "C21") (pin "1") (pinfunction "1_1") (pintype "passive"))
      (node (ref "C22") (pin "1") (pinfunction "1_1") (pintype "passive"))
      (node (ref "C23") (pin "1") (pinfunction "1_1") (pintype "passive"))
      (node (ref "C24") (pin "1") (pinfunction "1_1") (pintype "passive"))
      (node (ref "C25") (pin "1") (pinfunction "1_1") (pintype "passive"))
      (node (ref "C26") (pin "1") (pinfunction "1_1") (pintype "passive"))
      (node (ref "C27") (pin "1") (pinfunction "1_1") (pintype "passive"))
      (node (ref "C28") (pin "1") (pinfunction "1_1") (pintype "passive"))
      (node (ref "C30") (pin "1") (pinfunction "1_1") (pintype "passive"))
      (node (ref "C31") (pin "1") (pinfunction "1_1") (pintype "passive"))
      (node (ref "C33") (pin "1") (pinfunction "1_1") (pintype "passive"))
      (node (ref "C34") (pin "1") (pinfunction "1_1") (pintype "passive"))
      (node (ref "C35") (pin "1") (pinfunction "1_1") (pintype "passive"))
      (node (ref "C36") (pin "1") (pinfunction "1_1") (pintype "passive"))
      (node (ref "C37") (pin "1") (pinfunction "1_1") (pintype "passive"))
      (node (ref "C38") (pin "1") (pinfunction "1_1") (pintype "passive"))
      (node (ref "C39") (pin "1") (pinfunction "1_1") (pintype "passive"))
      (node (ref "C40") (pin "1") (pinfunction "1_1") (pintype "passive"))
      (node (ref "C6") (pin "1") (pinfunction "1_1") (pintype "passive"))
      (node (ref "LED1") (pin "1-VDD") (pinfunction "VDD_1-VDD") (pintype "power_in"))
      (node (ref "LED10") (pin "1-VDD") (pinfunction "VDD_1-VDD") (pintype "power_in"))
      (node (ref "LED11") (pin "1-VDD") (pinfunction "VDD_1-VDD") (pintype "power_in"))
      (node (ref "LED12") (pin "1-VDD") (pinfunction "VDD_1-VDD") (pintype "power_in"))
      (node (ref "LED13") (pin "1-VDD") (pinfunction "VDD_1-VDD") (pintype "power_in"))
      (node (ref "LED14") (pin "1-VDD") (pinfunction "VDD_1-VDD") (pintype "power_in"))
      (node (ref "LED15") (pin "1-VDD") (pinfunction "VDD_1-VDD") (pintype "power_in"))
      (node (ref "LED16") (pin "1-VDD") (pinfunction "VDD_1-VDD") (pintype "power_in"))
      (node (ref "LED17") (pin "1-VDD") (pinfunction "VDD_1-VDD") (pintype "power_in"))
      (node (ref "LED18") (pin "1-VDD") (pinfunction "VDD_1-VDD") (pintype "power_in"))
      (node (ref "LED19") (pin "1-VDD") (pinfunction "VDD_1-VDD") (pintype "power_in"))
      (node (ref "LED2") (pin "1-VDD") (pinfunction "VDD_1-VDD") (pintype "power_in"))
      (node (ref "LED20") (pin "1-VDD") (pinfunction "VDD_1-VDD") (pintype "power_in"))
      (node (ref "LED21") (pin "1-VDD") (pinfunction "VDD_1-VDD") (pintype "power_in"))
      (node (ref "LED22") (pin "1-VDD") (pinfunction "VDD_1-VDD") (pintype "power_in"))
      (node (ref "LED23") (pin "1-VDD") (pinfunction "VDD_1-VDD") (pintype "power_in"))
      (node (ref "LED24") (pin "1-VDD") (pinfunction "VDD_1-VDD") (pintype "power_in"))
      (node (ref "LED3") (pin "1-VDD") (pinfunction "VDD_1-VDD") (pintype "power_in"))
      (node (ref "LED4") (pin "1-VDD") (pinfunction "VDD_1-VDD") (pintype "power_in"))
      (node (ref "LED5") (pin "1-VDD") (pinfunction "VDD_1-VDD") (pintype "power_in"))
      (node (ref "LED6") (pin "1-VDD") (pinfunction "VDD_1-VDD") (pintype "power_in"))
      (node (ref "LED7") (pin "1-VDD") (pinfunction "VDD_1-VDD") (pintype "power_in"))
      (node (ref "LED8") (pin "1-VDD") (pinfunction "VDD_1-VDD") (pintype "power_in"))
      (node (ref "LED9") (pin "1-VDD") (pinfunction "VDD_1-VDD") (pintype "power_in"))
      (node (ref "NEO_PIX2") (pin "1") (pinfunction "1_1") (pintype "passive"))
      (node (ref "PWR_REG") (pin "VOUT") (pinfunction "VOUT_VOUT") (pintype "bidirectional"))
      (node (ref "U$3") (pin "VIN") (pinfunction "VIN_VIN") (pintype "power_in"))
      (node (ref "U$5") (pin "13") (pinfunction "VDD_13") (pintype "bidirectional"))
      (node (ref "U$5") (pin "16") (pinfunction "PVDDR1_16") (pintype "bidirectional"))
      (node (ref "U$5") (pin "21") (pinfunction "PVDDR2_21") (pintype "bidirectional"))
      (node (ref "U$5") (pin "4") (pinfunction "PVDDL1_4") (pintype "bidirectional"))
      (node (ref "U$5") (pin "9") (pinfunction "PVDDL2_9") (pintype "bidirectional"))
    )
    (net (code "42") (name "GND") (class "Default")
      (node (ref "BT2") (pin "GND@1") (pinfunction "-_GND@1") (pintype "power_in"))
      (node (ref "C1") (pin "-") (pinfunction "-_-") (pintype "passive"))
      (node (ref "C10") (pin "2") (pinfunction "2_2") (pintype "passive"))
      (node (ref "C11") (pin "2") (pinfunction "2_2") (pintype "passive"))
      (node (ref "C12") (pin "2") (pinfunction "2_2") (pintype "passive"))
      (node (ref "C13") (pin "2") (pinfunction "2_2") (pintype "passive"))
      (node (ref "C14") (pin "2") (pinfunction "2_2") (pintype "passive"))
      (node (ref "C15") (pin "2") (pinfunction "2_2") (pintype "passive"))
      (node (ref "C16") (pin "2") (pinfunction "2_2") (pintype "passive"))
      (node (ref "C17") (pin "2") (pinfunction "2_2") (pintype "passive"))
      (node (ref "C18") (pin "2") (pinfunction "2_2") (pintype "passive"))
      (node (ref "C19") (pin "2") (pinfunction "2_2") (pintype "passive"))
      (node (ref "C2") (pin "-") (pinfunction "-_-") (pintype "passive"))
      (node (ref "C20") (pin "2") (pinfunction "2_2") (pintype "passive"))
      (node (ref "C21") (pin "2") (pinfunction "2_2") (pintype "passive"))
      (node (ref "C22") (pin "2") (pinfunction "2_2") (pintype "passive"))
      (node (ref "C23") (pin "2") (pinfunction "2_2") (pintype "passive"))
      (node (ref "C24") (pin "2") (pinfunction "2_2") (pintype "passive"))
      (node (ref "C25") (pin "2") (pinfunction "2_2") (pintype "passive"))
      (node (ref "C26") (pin "2") (pinfunction "2_2") (pintype "passive"))
      (node (ref "C27") (pin "2") (pinfunction "2_2") (pintype "passive"))
      (node (ref "C28") (pin "2") (pinfunction "2_2") (pintype "passive"))
      (node (ref "C30") (pin "2") (pinfunction "2_2") (pintype "passive"))
      (node (ref "C31") (pin "2") (pinfunction "2_2") (pintype "passive"))
      (node (ref "C32") (pin "2") (pinfunction "2_2") (pintype "passive"))
      (node (ref "C33") (pin "2") (pinfunction "2_2") (pintype "passive"))
      (node (ref "C34") (pin "2") (pinfunction "2_2") (pintype "passive"))
      (node (ref "C35") (pin "2") (pinfunction "2_2") (pintype "passive"))
      (node (ref "C36") (pin "2") (pinfunction "2_2") (pintype "passive"))
      (node (ref "C37") (pin "2") (pinfunction "2_2") (pintype "passive"))
      (node (ref "C38") (pin "2") (pinfunction "2_2") (pintype "passive"))
      (node (ref "C39") (pin "2") (pinfunction "2_2") (pintype "passive"))
      (node (ref "C40") (pin "2") (pinfunction "2_2") (pintype "passive"))
      (node (ref "C48") (pin "2") (pinfunction "2_2") (pintype "passive"))
      (node (ref "C49") (pin "2") (pinfunction "2_2") (pintype "passive"))
      (node (ref "C5") (pin "2") (pinfunction "2_2") (pintype "passive"))
      (node (ref "C50") (pin "2") (pinfunction "2_2") (pintype "passive"))
      (node (ref "C57") (pin "2") (pinfunction "2_2") (pintype "passive"))
      (node (ref "C58") (pin "2") (pinfunction "2_2") (pintype "passive"))
      (node (ref "C59") (pin "2") (pinfunction "2_2") (pintype "passive"))
      (node (ref "C6") (pin "2") (pinfunction "2_2") (pintype "passive"))
      (node (ref "C60") (pin "2") (pinfunction "2_2") (pintype "passive"))
      (node (ref "C7") (pin "2") (pinfunction "2_2") (pintype "passive"))
      (node (ref "C8") (pin "2") (pinfunction "2_2") (pintype "passive"))
      (node (ref "C9") (pin "2") (pinfunction "2_2") (pintype "passive"))
      (node (ref "J7") (pin "6") (pinfunction "VSS_6") (pintype "passive"))
      (node (ref "J7") (pin "S1") (pinfunction "GND_S1") (pintype "passive"))
      (node (ref "J7") (pin "S2") (pinfunction "GND_S2") (pintype "passive"))
      (node (ref "J7") (pin "S3") (pinfunction "GND_S3") (pintype "passive"))
      (node (ref "J7") (pin "S5") (pinfunction "GND_S5") (pintype "passive"))
      (node (ref "LED1") (pin "3-GND") (pinfunction "GND_3-GND") (pintype "power_in"))
      (node (ref "LED10") (pin "3-GND") (pinfunction "GND_3-GND") (pintype "power_in"))
      (node (ref "LED11") (pin "3-GND") (pinfunction "GND_3-GND") (pintype "power_in"))
      (node (ref "LED12") (pin "3-GND") (pinfunction "GND_3-GND") (pintype "power_in"))
      (node (ref "LED13") (pin "3-GND") (pinfunction "GND_3-GND") (pintype "power_in"))
      (node (ref "LED14") (pin "3-GND") (pinfunction "GND_3-GND") (pintype "power_in"))
      (node (ref "LED15") (pin "3-GND") (pinfunction "GND_3-GND") (pintype "power_in"))
      (node (ref "LED16") (pin "3-GND") (pinfunction "GND_3-GND") (pintype "power_in"))
      (node (ref "LED17") (pin "3-GND") (pinfunction "GND_3-GND") (pintype "power_in"))
      (node (ref "LED18") (pin "3-GND") (pinfunction "GND_3-GND") (pintype "power_in"))
      (node (ref "LED19") (pin "3-GND") (pinfunction "GND_3-GND") (pintype "power_in"))
      (node (ref "LED2") (pin "3-GND") (pinfunction "GND_3-GND") (pintype "power_in"))
      (node (ref "LED20") (pin "3-GND") (pinfunction "GND_3-GND") (pintype "power_in"))
      (node (ref "LED21") (pin "3-GND") (pinfunction "GND_3-GND") (pintype "power_in"))
      (node (ref "LED22") (pin "3-GND") (pinfunction "GND_3-GND") (pintype "power_in"))
      (node (ref "LED23") (pin "3-GND") (pinfunction "GND_3-GND") (pintype "power_in"))
      (node (ref "LED24") (pin "3-GND") (pinfunction "GND_3-GND") (pintype "power_in"))
      (node (ref "LED3") (pin "3-GND") (pinfunction "GND_3-GND") (pintype "power_in"))
      (node (ref "LED4") (pin "3-GND") (pinfunction "GND_3-GND") (pintype "power_in"))
      (node (ref "LED5") (pin "3-GND") (pinfunction "GND_3-GND") (pintype "power_in"))
      (node (ref "LED6") (pin "3-GND") (pinfunction "GND_3-GND") (pintype "power_in"))
      (node (ref "LED7") (pin "3-GND") (pinfunction "GND_3-GND") (pintype "power_in"))
      (node (ref "LED8") (pin "3-GND") (pinfunction "GND_3-GND") (pintype "power_in"))
      (node (ref "LED9") (pin "3-GND") (pinfunction "GND_3-GND") (pintype "power_in"))
      (node (ref "MEMS1") (pin "2") (pinfunction "SELECT_2") (pintype "input"))
      (node (ref "MEMS1") (pin "P$1") (pinfunction "GND_P$1") (pintype "power_in"))
      (node (ref "NEO_PIX2") (pin "3") (pinfunction "3_3") (pintype "passive"))
      (node (ref "PWR_REG") (pin "GND") (pinfunction "GND_GND") (pintype "bidirectional"))
      (node (ref "S1") (pin "1") (pinfunction "1_1") (pintype "passive"))
      (node (ref "S1") (pin "2") (pinfunction "2_2") (pintype "passive"))
      (node (ref "S1") (pin "3") (pinfunction "3_3") (pintype "passive"))
      (node (ref "S1") (pin "4") (pinfunction "4_4") (pintype "passive"))
      (node (ref "S1") (pin "5") (pinfunction "5_5") (pintype "passive"))
      (node (ref "S1") (pin "6") (pinfunction "6_6") (pintype "passive"))
      (node (ref "S1") (pin "7") (pinfunction "7_7") (pintype "passive"))
      (node (ref "S1") (pin "8") (pinfunction "8_8") (pintype "passive"))
      (node (ref "S2") (pin "1") (pinfunction "O_1") (pintype "passive"))
      (node (ref "U$3") (pin "GND") (pinfunction "GND_GND") (pintype "power_in"))
      (node (ref "U$5") (pin "18") (pinfunction "PGNDR1_18") (pintype "bidirectional"))
      (node (ref "U$5") (pin "19") (pinfunction "PGNDR2_19") (pintype "bidirectional"))
      (node (ref "U$5") (pin "6") (pinfunction "PGNDL1_6") (pintype "bidirectional"))
      (node (ref "U$5") (pin "7") (pinfunction "PGNDL2_7") (pintype "bidirectional"))
      (node (ref "U$8") (pin "CTRL_ADR0_CS") (pinfunction "ADDR_CTRL_ADR0_CS") (pintype "bidirectional"))
      (node (ref "U$8") (pin "CTRL_MODE") (pinfunction "MODE_CTRL_MODE") (pintype "bidirectional"))
      (node (ref "U$8") (pin "GND1") (pinfunction "GND1_GND1") (pintype "bidirectional"))
      (node (ref "U$8") (pin "GND2") (pinfunction "GND2_GND2") (pintype "bidirectional"))
      (node (ref "U$8") (pin "GND3") (pinfunction "GND3_GND3") (pintype "bidirectional"))
      (node (ref "U$9") (pin "3") (pinfunction "GND_3") (pintype "bidirectional"))
      (node (ref "U2") (pin "4") (pinfunction "VSS_4") (pintype "bidirectional"))
      (node (ref "U2") (pin "5") (pinfunction "VSS_5") (pintype "bidirectional"))
      (node (ref "VEML1") (pin "3") (pinfunction "GND_3") (pintype "bidirectional"))
      (node (ref "VMEL1") (pin "1") (pinfunction "GND_1") (pintype "power_in"))
      (node (ref "VMEL1") (pin "4") (pinfunction "ADDR_4") (pintype "bidirectional"))
    )
    (net (code "43") (name "Net-(BT1--)") (class "Default")
      (node (ref "BT1") (pin "GND@1") (pinfunction "-_GND@1") (pintype "power_in"))
      (node (ref "BT2") (pin "PWR@1") (pinfunction "+_PWR@1") (pintype "power_in"))
    )
    (net (code "44") (name "Net-(C48-Pad1)") (class "Default")
      (node (ref "C48") (pin "1") (pinfunction "1_1") (pintype "passive"))
      (node (ref "C49") (pin "1") (pinfunction "1_1") (pintype "passive"))
      (node (ref "FERRITE1") (pin "2") (pinfunction "2_2") (pintype "passive"))
      (node (ref "U$8") (pin "VDDD") (pinfunction "VDDD_VDDD") (pintype "bidirectional"))
      (node (ref "U$8") (pin "VDDIO") (pinfunction "VDDIO_VDDIO") (pintype "bidirectional"))
    )
    (net (code "45") (name "Net-(C57-Pad1)") (class "Default")
      (node (ref "C57") (pin "1") (pinfunction "1_1") (pintype "passive"))
      (node (ref "U$8") (pin "VAG") (pinfunction "VAG_VAG") (pintype "bidirectional"))
    )
    (net (code "46") (name "Net-(J1-Pad2)") (class "Default")
      (node (ref "J1") (pin "2") (pinfunction "2_2") (pintype "passive"))
      (node (ref "MIC1") (pin "1") (pinfunction "1_1") (pintype "passive"))
    )
    (net (code "47") (name "Net-(J2-Pad2)") (class "Default")
      (node (ref "J2") (pin "2") (pinfunction "2_2") (pintype "passive"))
      (node (ref "MIC2") (pin "1") (pinfunction "1_1") (pintype "passive"))
    )
    (net (code "48") (name "Net-(J3-Pad2)") (class "Default")
      (node (ref "J3") (pin "2") (pinfunction "2_2") (pintype "passive"))
      (node (ref "MIC3") (pin "1") (pinfunction "1_1") (pintype "passive"))
    )
    (net (code "49") (name "Net-(J4-Pad2)") (class "Default")
      (node (ref "J4") (pin "2") (pinfunction "2_2") (pintype "passive"))
      (node (ref "MIC4") (pin "1") (pinfunction "1_1") (pintype "passive"))
    )
    (net (code "50") (name "Net-(J5-Pad2)") (class "Default")
      (node (ref "J5") (pin "2") (pinfunction "2_2") (pintype "passive"))
      (node (ref "MIC5") (pin "1") (pinfunction "1_1") (pintype "passive"))
    )
    (net (code "51") (name "Net-(J6-Pad2)") (class "Default")
      (node (ref "J6") (pin "2") (pinfunction "2_2") (pintype "passive"))
      (node (ref "MIC1") (pin "2") (pinfunction "2_2") (pintype "passive"))
    )
    (net (code "52") (name "Net-(J8-Pad2)") (class "Default")
      (node (ref "J8") (pin "2") (pinfunction "2_2") (pintype "passive"))
      (node (ref "MIC2") (pin "2") (pinfunction "2_2") (pintype "passive"))
    )
    (net (code "53") (name "Net-(J9-Pad2)") (class "Default")
      (node (ref "J9") (pin "2") (pinfunction "2_2") (pintype "passive"))
      (node (ref "MIC3") (pin "2") (pinfunction "2_2") (pintype "passive"))
    )
    (net (code "54") (name "Net-(J10-Pad2)") (class "Default")
      (node (ref "J10") (pin "2") (pinfunction "2_2") (pintype "passive"))
      (node (ref "MIC4") (pin "2") (pinfunction "2_2") (pintype "passive"))
    )
    (net (code "55") (name "Net-(J11-Pad2)") (class "Default")
      (node (ref "J11") (pin "2") (pinfunction "2_2") (pintype "passive"))
      (node (ref "MIC5") (pin "2") (pinfunction "2_2") (pintype "passive"))
    )
    (net (code "56") (name "Net-(LED1-DO)") (class "Default")
      (node (ref "LED1") (pin "2-DOUT") (pinfunction "DO_2-DOUT") (pintype "output"))
      (node (ref "LED2") (pin "4-DIN") (pinfunction "DI_4-DIN") (pintype "input"))
    )
    (net (code "57") (name "Net-(LED2-DO)") (class "Default")
      (node (ref "LED2") (pin "2-DOUT") (pinfunction "DO_2-DOUT") (pintype "output"))
      (node (ref "LED3") (pin "4-DIN") (pinfunction "DI_4-DIN") (pintype "input"))
    )
    (net (code "58") (name "Net-(LED3-DO)") (class "Default")
      (node (ref "LED3") (pin "2-DOUT") (pinfunction "DO_2-DOUT") (pintype "output"))
      (node (ref "LED4") (pin "4-DIN") (pinfunction "DI_4-DIN") (pintype "input"))
    )
    (net (code "59") (name "Net-(LED4-DO)") (class "Default")
      (node (ref "LED4") (pin "2-DOUT") (pinfunction "DO_2-DOUT") (pintype "output"))
      (node (ref "LED5") (pin "4-DIN") (pinfunction "DI_4-DIN") (pintype "input"))
    )
    (net (code "60") (name "Net-(LED5-DO)") (class "Default")
      (node (ref "LED5") (pin "2-DOUT") (pinfunction "DO_2-DOUT") (pintype "output"))
      (node (ref "LED6") (pin "4-DIN") (pinfunction "DI_4-DIN") (pintype "input"))
    )
    (net (code "61") (name "Net-(LED6-DO)") (class "Default")
      (node (ref "LED6") (pin "2-DOUT") (pinfunction "DO_2-DOUT") (pintype "output"))
      (node (ref "LED7") (pin "4-DIN") (pinfunction "DI_4-DIN") (pintype "input"))
    )
    (net (code "62") (name "Net-(LED7-DO)") (class "Default")
      (node (ref "LED7") (pin "2-DOUT") (pinfunction "DO_2-DOUT") (pintype "output"))
      (node (ref "LED8") (pin "4-DIN") (pinfunction "DI_4-DIN") (pintype "input"))
    )
    (net (code "63") (name "Net-(LED8-DO)") (class "Default")
      (node (ref "LED8") (pin "2-DOUT") (pinfunction "DO_2-DOUT") (pintype "output"))
      (node (ref "LED9") (pin "4-DIN") (pinfunction "DI_4-DIN") (pintype "input"))
    )
    (net (code "64") (name "Net-(LED10-DI)") (class "Default")
      (node (ref "LED10") (pin "4-DIN") (pinfunction "DI_4-DIN") (pintype "input"))
      (node (ref "LED9") (pin "2-DOUT") (pinfunction "DO_2-DOUT") (pintype "output"))
    )
    (net (code "65") (name "Net-(LED10-DO)") (class "Default")
      (node (ref "LED10") (pin "2-DOUT") (pinfunction "DO_2-DOUT") (pintype "output"))
      (node (ref "LED11") (pin "4-DIN") (pinfunction "DI_4-DIN") (pintype "input"))
    )
    (net (code "66") (name "Net-(LED11-DO)") (class "Default")
      (node (ref "LED11") (pin "2-DOUT") (pinfunction "DO_2-DOUT") (pintype "output"))
      (node (ref "LED12") (pin "4-DIN") (pinfunction "DI_4-DIN") (pintype "input"))
    )
    (net (code "67") (name "Net-(LED12-DO)") (class "Default")
      (node (ref "LED12") (pin "2-DOUT") (pinfunction "DO_2-DOUT") (pintype "output"))
      (node (ref "LED13") (pin "4-DIN") (pinfunction "DI_4-DIN") (pintype "input"))
    )
    (net (code "68") (name "Net-(LED13-DO)") (class "Default")
      (node (ref "LED13") (pin "2-DOUT") (pinfunction "DO_2-DOUT") (pintype "output"))
      (node (ref "LED14") (pin "4-DIN") (pinfunction "DI_4-DIN") (pintype "input"))
    )
    (net (code "69") (name "Net-(LED14-DO)") (class "Default")
      (node (ref "LED14") (pin "2-DOUT") (pinfunction "DO_2-DOUT") (pintype "output"))
      (node (ref "LED15") (pin "4-DIN") (pinfunction "DI_4-DIN") (pintype "input"))
    )
    (net (code "70") (name "Net-(LED15-DO)") (class "Default")
      (node (ref "LED15") (pin "2-DOUT") (pinfunction "DO_2-DOUT") (pintype "output"))
      (node (ref "LED16") (pin "4-DIN") (pinfunction "DI_4-DIN") (pintype "input"))
    )
    (net (code "71") (name "Net-(LED17-DO)") (class "Default")
      (node (ref "LED17") (pin "2-DOUT") (pinfunction "DO_2-DOUT") (pintype "output"))
      (node (ref "LED18") (pin "4-DIN") (pinfunction "DI_4-DIN") (pintype "input"))
    )
    (net (code "72") (name "Net-(LED18-DO)") (class "Default")
      (node (ref "LED18") (pin "2-DOUT") (pinfunction "DO_2-DOUT") (pintype "output"))
      (node (ref "LED19") (pin "4-DIN") (pinfunction "DI_4-DIN") (pintype "input"))
    )
    (net (code "73") (name "Net-(LED19-DO)") (class "Default")
      (node (ref "LED19") (pin "2-DOUT") (pinfunction "DO_2-DOUT") (pintype "output"))
      (node (ref "LED20") (pin "4-DIN") (pinfunction "DI_4-DIN") (pintype "input"))
    )
    (net (code "74") (name "Net-(LED20-DO)") (class "Default")
      (node (ref "LED20") (pin "2-DOUT") (pinfunction "DO_2-DOUT") (pintype "output"))
      (node (ref "LED21") (pin "4-DIN") (pinfunction "DI_4-DIN") (pintype "input"))
    )
    (net (code "75") (name "Net-(LED21-DO)") (class "Default")
      (node (ref "LED21") (pin "2-DOUT") (pinfunction "DO_2-DOUT") (pintype "output"))
      (node (ref "LED22") (pin "4-DIN") (pinfunction "DI_4-DIN") (pintype "input"))
    )
    (net (code "76") (name "Net-(LED22-DO)") (class "Default")
      (node (ref "LED22") (pin "2-DOUT") (pinfunction "DO_2-DOUT") (pintype "output"))
      (node (ref "LED23") (pin "4-DIN") (pinfunction "DI_4-DIN") (pintype "input"))
    )
    (net (code "77") (name "Net-(LED23-DO)") (class "Default")
      (node (ref "LED23") (pin "2-DOUT") (pinfunction "DO_2-DOUT") (pintype "output"))
      (node (ref "LED24") (pin "4-DIN") (pinfunction "DI_4-DIN") (pintype "input"))
    )
    (net (code "78") (name "Net-(MEMS1-DATA_OUT)") (class "Default")
      (node (ref "MEMS1") (pin "6") (pinfunction "DATA_OUT_6") (pintype "output"))
      (node (ref "R2") (pin "1") (pinfunction "1_1") (pintype "passive"))
    )
    (net (code "79") (name "Net-(S2-P)") (class "Default")
      (node (ref "PWR_REG") (pin "EN") (pinfunction "EN_EN") (pintype "bidirectional"))
      (node (ref "S2") (pin "2") (pinfunction "P_2") (pintype "passive"))
    )
    (net (code "80") (name "Net-(U$8-LINEOUTL)") (class "Default")
      (node (ref "C54") (pin "1") (pinfunction "1_1") (pintype "passive"))
      (node (ref "U$8") (pin "LINEOUT_L") (pinfunction "LINEOUTL_LINEOUT_L") (pintype "bidirectional"))
    )
    (net (code "81") (name "Net-(U$8-LINEOUTR)") (class "Default")
      (node (ref "C53") (pin "1") (pinfunction "1_1") (pintype "passive"))
      (node (ref "U$8") (pin "LINEOUT_R") (pinfunction "LINEOUTR_LINEOUT_R") (pintype "bidirectional"))
    )
    (net (code "82") (name "Net-(U$8-MCLK)") (class "Default")
      (node (ref "R9") (pin "2") (pinfunction "2_2") (pintype "passive"))
      (node (ref "U$8") (pin "SYS_MCLK") (pinfunction "MCLK_SYS_MCLK") (pintype "bidirectional"))
    )
    (net (code "83") (name "Net-(U$8-RX)") (class "Default")
      (node (ref "DIN") (pin "2") (pinfunction "2_2") (pintype "passive"))
      (node (ref "U$8") (pin "I2S_DIN") (pinfunction "RX_I2S_DIN") (pintype "bidirectional"))
    )
    (net (code "84") (name "Net-(U$8-TX)") (class "Default")
      (node (ref "DOUT") (pin "2") (pinfunction "2_2") (pintype "passive"))
      (node (ref "U$8") (pin "I2S_DOUT") (pinfunction "TX_I2S_DOUT") (pintype "bidirectional"))
    )
    (net (code "85") (name "Net-(U$9-OUT)") (class "Default")
      (node (ref "C50") (pin "1") (pinfunction "1_1") (pintype "passive"))
      (node (ref "U$8") (pin "VDDA") (pinfunction "VDDA_VDDA") (pintype "bidirectional"))
      (node (ref "U$9") (pin "2") (pinfunction "OUT_2") (pintype "bidirectional"))
    )
    (net (code "86") (name "Net-(VEML1-VDD)") (class "Default")
      (node (ref "C10") (pin "1") (pinfunction "1_1") (pintype "passive"))
      (node (ref "C8") (pin "1") (pinfunction "1_1") (pintype "passive"))
      (node (ref "R1") (pin "1") (pinfunction "1_1") (pintype "passive"))
      (node (ref "VEML1") (pin "2") (pinfunction "VDD_2") (pintype "bidirectional"))
      (node (ref "VMEL1") (pin "6") (pinfunction "VDD_6") (pintype "power_in"))
    )
    (net (code "87") (name "unconnected-(J7-CD_SW-Pad9)") (class "Default")
      (node (ref "J7") (pin "9") (pinfunction "CD_SW_9") (pintype "passive"))
    )
    (net (code "88") (name "unconnected-(J7-DAT1-Pad8)") (class "Default")
      (node (ref "J7") (pin "8") (pinfunction "DAT1_8") (pintype "passive"))
    )
    (net (code "89") (name "unconnected-(J7-DAT2-Pad1)") (class "Default")
      (node (ref "J7") (pin "1") (pinfunction "DAT2_1") (pintype "passive"))
    )
    (net (code "90") (name "unconnected-(LED24-DO-Pad2-DOUT)") (class "Default")
      (node (ref "LED24") (pin "2-DOUT") (pinfunction "DO_2-DOUT") (pintype "output"))
    )
    (net (code "91") (name "unconnected-(PWR_REG-PadPG)") (class "Default")
      (node (ref "PWR_REG") (pin "PG") (pinfunction "PG_PG") (pintype "bidirectional"))
    )
    (net (code "92") (name "unconnected-(PWR_REG-PadSEL)") (class "Default")
      (node (ref "PWR_REG") (pin "SEL") (pinfunction "SEL_SEL") (pintype "bidirectional"))
    )
    (net (code "93") (name "unconnected-(S2-S-Pad3)") (class "Default")
      (node (ref "S2") (pin "3") (pinfunction "S_3") (pintype "passive"))
    )
    (net (code "94") (name "unconnected-(U$5-NC-Pad15)") (class "Default")
      (node (ref "U$5") (pin "15") (pinfunction "NC_15") (pintype "bidirectional"))
    )
    (net (code "95") (name "unconnected-(U$8-HPL-PadHP_L)") (class "Default")
      (node (ref "U$8") (pin "HP_L") (pinfunction "HPL_HP_L") (pintype "bidirectional"))
    )
    (net (code "96") (name "unconnected-(U$8-HPR-PadHP_R)") (class "Default")
      (node (ref "U$8") (pin "HP_R") (pinfunction "HPR_HP_R") (pintype "bidirectional"))
    )
    (net (code "97") (name "unconnected-(U$8-HPVGND-PadHP_VGND)") (class "Default")
      (node (ref "U$8") (pin "HP_VGND") (pinfunction "HPVGND_HP_VGND") (pintype "bidirectional"))
    )
    (net (code "98") (name "unconnected-(U$8-LINEINL-PadLININ_L)") (class "Default")
      (node (ref "U$8") (pin "LININ_L") (pinfunction "LINEINL_LININ_L") (pintype "bidirectional"))
    )
    (net (code "99") (name "unconnected-(U$8-LINEINR-PadLININ_R)") (class "Default")
      (node (ref "U$8") (pin "LININ_R") (pinfunction "LINEINR_LININ_R") (pintype "bidirectional"))
    )
    (net (code "100") (name "unconnected-(U$8-MICBIAS-PadMIC_BIAS)") (class "Default")
      (node (ref "U$8") (pin "MIC_BIAS") (pinfunction "MICBIAS_MIC_BIAS") (pintype "bidirectional"))
    )
    (net (code "101") (name "unconnected-(U$8-PadCPFILT)") (class "Default")
      (node (ref "U$8") (pin "CPFILT") (pinfunction "CPFILT_CPFILT") (pintype "bidirectional"))
    )
    (net (code "102") (name "unconnected-(U$8-PadMIC)") (class "Default")
      (node (ref "U$8") (pin "MIC") (pinfunction "MIC_MIC") (pintype "bidirectional"))
    )
  )
)
